# Power_Supply.net
KiCad netlist of a schematic drawn in Altium Designer
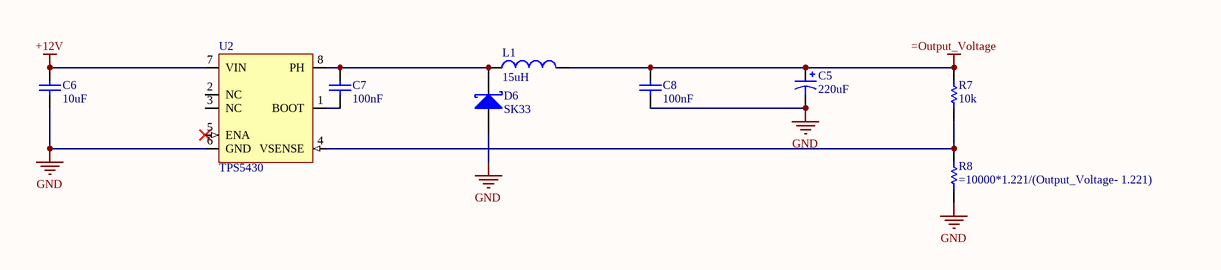
[diagram p0: Power_Supply.SchDoc]

(export (version "E")
  (design (tool "Eeschema 10.0.6"))
  (components
    (comp (ref "C5")
      (value "220uF")
      (footprint "CAP_SMD_D_IPC_MD")
      (description "Polarized Capacitor (Axial)")
      (fields (field (name "Comment") "Cap Pol") (field (name "PUBLISHER") "Altium Limited"))
      (libsource (lib "DataLogger") (part "Cap Pol"))
    )
    (comp (ref "C6")
      (value "10uF")
      (footprint "CAP_0805_IPC_MD")
      (description "Capacitor")
      (fields (field (name "Comment") "Cap"))
      (libsource (lib "DataLogger") (part "Cap"))
    )
    (comp (ref "C7")
      (value "100nF")
      (footprint "CAP_0805_IPC_MD")
      (description "Capacitor")
      (fields (field (name "Comment") "Cap"))
      (libsource (lib "DataLogger") (part "Cap"))
    )
    (comp (ref "C8")
      (value "100nF")
      (footprint "CAP_0805_IPC_MD")
      (description "Capacitor")
      (fields (field (name "Comment") "Cap"))
      (libsource (lib "DataLogger") (part "Cap"))
    )
    (comp (ref "D6")
      (value "SK33")
      (footprint "DO214AB_IPC_MD")
      (description "Schottky Diode")
      (fields (field (name "MANUFACTURER") "Diotec") (field (name "MANUFACTURERNAME") "SK33"))
      (libsource (lib "DataLogger") (part "SK33"))
    )
    (comp (ref "L1")
      (value "15uH")
      (footprint "DL50")
      (description "Inductor")
      (fields (field (name "MANUFACTURER") "Ferrocore"))
      (libsource (lib "DataLogger") (part "Inductor"))
    )
    (comp (ref "R7")
      (value "10k")
      (footprint "RES_0805_IPC_MD")
      (description "Resistor")
      (fields (field (name "MANUFACTURER") "Royal Ohm") (field (name "Comment") "Res"))
      (libsource (lib "DataLogger") (part "Res"))
    )
    (comp (ref "R8")
      (value "Res")
      (footprint "RES_0805_IPC_MD")
      (description "Resistor")
      (fields (field (name "MANUFACTURER") "Royal Ohm"))
      (libsource (lib "DataLogger") (part "Res"))
    )
    (comp (ref "U2")
      (value "TPS5430")
      (footprint "DataLogger:SOIC_8_THERMAL_PAD_IPC_MD")
      (description "3-A, Wide Input Range, Step-Down Converter")
      (fields (field (name "MANUFACTURER") "Texas Instruments"))
      (libsource (lib "DataLogger") (part "TPS5430"))
    )
  )
  (nets
    (net (code "1") (name "+12V") (class "Default")
      (node (ref "C6") (pin "2") (pinfunction "2_2") (pintype "passive"))
      (node (ref "U2") (pin "7") (pinfunction "VIN_7") (pintype "power_in"))
    )
    (net (code "2") (name "6") (class "Default")
      (node (ref "U2") (pin "9") (pinfunction "PwPd_9") (pintype "passive"))
    )
    (net (code "3") (name "=Output_Voltage") (class "Default")
      (node (ref "C5") (pin "1") (pinfunction "1_1") (pintype "passive"))
      (node (ref "C8") (pin "2") (pinfunction "2_2") (pintype "passive"))
      (node (ref "L1") (pin "2") (pinfunction "2_2") (pintype "passive"))
      (node (ref "R7") (pin "2") (pinfunction "2_2") (pintype "passive"))
    )
    (net (code "4") (name "GND") (class "Default")
      (node (ref "C5") (pin "2") (pinfunction "2_2") (pintype "passive"))
      (node (ref "C6") (pin "1") (pinfunction "1_1") (pintype "passive"))
      (node (ref "C8") (pin "1") (pinfunction "1_1") (pintype "passive"))
      (node (ref "D6") (pin "1") (pinfunction "A_1") (pintype "passive"))
      (node (ref "R8") (pin "1") (pinfunction "1_1") (pintype "passive"))
      (node (ref "U2") (pin "6") (pinfunction "GND_6") (pintype "power_in"))
    )
    (net (code "5") (name "Net-(D6-K)") (class "Default")
      (node (ref "C7") (pin "2") (pinfunction "2_2") (pintype "passive"))
      (node (ref "D6") (pin "2") (pinfunction "K_2") (pintype "passive"))
      (node (ref "L1") (pin "1") (pinfunction "1_1") (pintype "passive"))
      (node (ref "U2") (pin "8") (pinfunction "PH_8") (pintype "passive"))
    )
    (net (code "6") (name "Net-(U2-BOOT)") (class "Default")
      (node (ref "C7") (pin "1") (pinfunction "1_1") (pintype "passive"))
      (node (ref "U2") (pin "1") (pinfunction "BOOT_1") (pintype "passive"))
    )
    (net (code "7") (name "Net-(U2-VSENSE)") (class "Default")
      (node (ref "R7") (pin "1") (pinfunction "1_1") (pintype "passive"))
      (node (ref "R8") (pin "2") (pinfunction "2_2") (pintype "passive"))
      (node (ref "U2") (pin "4") (pinfunction "VSENSE_4") (pintype "input"))
    )
    (net (code "8") (name "unconnected-(U2-ENA-Pad5)") (class "Default")
      (node (ref "U2") (pin "5") (pinfunction "ENA_5") (pintype "input+no_connect"))
    )
    (net (code "9") (name "unconnected-(U2-NC-Pad2)") (class "Default")
      (node (ref "U2") (pin "2") (pinfunction "NC_2") (pintype "passive"))
    )
    (net (code "10") (name "unconnected-(U2-NC-Pad3)") (class "Default")
      (node (ref "U2") (pin "3") (pinfunction "NC_3") (pintype "passive"))
    )
  )
)
